# Solo_Board1.net
KiCad netlist of a schematic drawn in Altium Designer
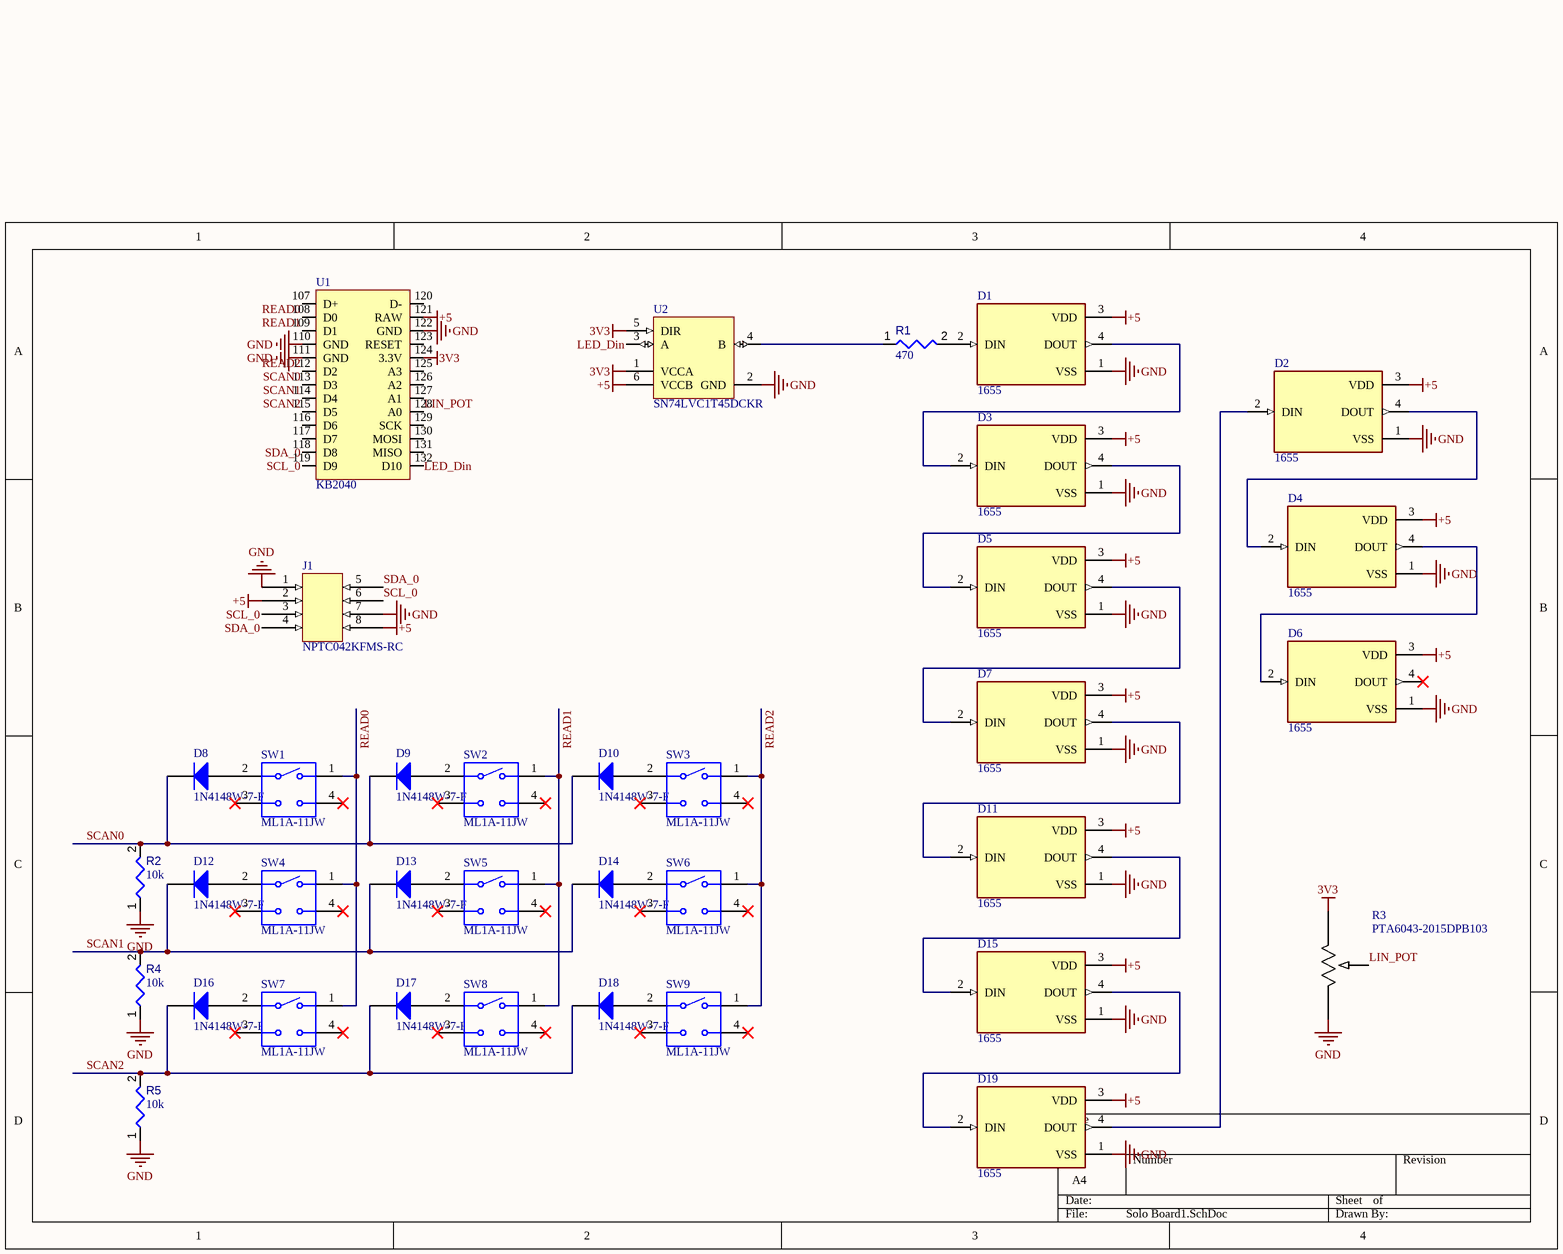
[diagram p0: Solo Board1.SchDoc]

(export (version "E")
  (design (tool "Eeschema 10.0.6"))
  (components
    (comp (ref "D1")
      (value "1655")
      (footprint "LED_1655")
      (description "Ws2812b 5050 Rgb Led With Integrated Driver Chip Pack Of 10")
      (libsource (lib "Joshua Lobe") (part "1655"))
    )
    (comp (ref "D2")
      (value "1655")
      (footprint "LED_1655")
      (description "Ws2812b 5050 Rgb Led With Integrated Driver Chip Pack Of 10")
      (libsource (lib "Joshua Lobe") (part "1655"))
    )
    (comp (ref "D3")
      (value "1655")
      (footprint "LED_1655")
      (description "Ws2812b 5050 Rgb Led With Integrated Driver Chip Pack Of 10")
      (libsource (lib "Joshua Lobe") (part "1655"))
    )
    (comp (ref "D4")
      (value "1655")
      (footprint "LED_1655")
      (description "Ws2812b 5050 Rgb Led With Integrated Driver Chip Pack Of 10")
      (libsource (lib "Joshua Lobe") (part "1655"))
    )
    (comp (ref "D5")
      (value "1655")
      (footprint "LED_1655")
      (description "Ws2812b 5050 Rgb Led With Integrated Driver Chip Pack Of 10")
      (libsource (lib "Joshua Lobe") (part "1655"))
    )
    (comp (ref "D6")
      (value "1655")
      (footprint "LED_1655")
      (description "Ws2812b 5050 Rgb Led With Integrated Driver Chip Pack Of 10")
      (libsource (lib "Joshua Lobe") (part "1655"))
    )
    (comp (ref "D7")
      (value "1655")
      (footprint "LED_1655")
      (description "Ws2812b 5050 Rgb Led With Integrated Driver Chip Pack Of 10")
      (libsource (lib "Joshua Lobe") (part "1655"))
    )
    (comp (ref "D8")
      (value "1N4148W-7-F")
      (footprint "DIOD-SOD123-2_V")
      (description "Fast Switching Diode, 100 V, 0.15 A, -65 to 150 degC, 2-Pin?SOD123, RoHS, Tape and Reel")
      (fields (field (name "MANUFACTURER") "DiodesIncorporated"))
      (libsource (lib "Altium Content Vault") (part "D-AK-2"))
    )
    (comp (ref "D9")
      (value "1N4148W-7-F")
      (footprint "DIOD-SOD123-2_V")
      (description "Fast Switching Diode, 100 V, 0.15 A, -65 to 150 degC, 2-Pin?SOD123, RoHS, Tape and Reel")
      (fields (field (name "MANUFACTURER") "DiodesIncorporated"))
      (libsource (lib "Altium Content Vault") (part "D-AK-2"))
    )
    (comp (ref "D10")
      (value "1N4148W-7-F")
      (footprint "DIOD-SOD123-2_V")
      (description "Fast Switching Diode, 100 V, 0.15 A, -65 to 150 degC, 2-Pin?SOD123, RoHS, Tape and Reel")
      (fields (field (name "MANUFACTURER") "DiodesIncorporated"))
      (libsource (lib "Altium Content Vault") (part "D-AK-2"))
    )
    (comp (ref "D11")
      (value "1655")
      (footprint "LED_1655")
      (description "Ws2812b 5050 Rgb Led With Integrated Driver Chip Pack Of 10")
      (libsource (lib "Joshua Lobe") (part "1655"))
    )
    (comp (ref "D12")
      (value "1N4148W-7-F")
      (footprint "DIOD-SOD123-2_V")
      (description "Fast Switching Diode, 100 V, 0.15 A, -65 to 150 degC, 2-Pin?SOD123, RoHS, Tape and Reel")
      (fields (field (name "MANUFACTURER") "DiodesIncorporated"))
      (libsource (lib "Altium Content Vault") (part "D-AK-2"))
    )
    (comp (ref "D13")
      (value "1N4148W-7-F")
      (footprint "DIOD-SOD123-2_V")
      (description "Fast Switching Diode, 100 V, 0.15 A, -65 to 150 degC, 2-Pin?SOD123, RoHS, Tape and Reel")
      (fields (field (name "MANUFACTURER") "DiodesIncorporated"))
      (libsource (lib "Altium Content Vault") (part "D-AK-2"))
    )
    (comp (ref "D14")
      (value "1N4148W-7-F")
      (footprint "DIOD-SOD123-2_V")
      (description "Fast Switching Diode, 100 V, 0.15 A, -65 to 150 degC, 2-Pin?SOD123, RoHS, Tape and Reel")
      (fields (field (name "MANUFACTURER") "DiodesIncorporated"))
      (libsource (lib "Altium Content Vault") (part "D-AK-2"))
    )
    (comp (ref "D15")
      (value "1655")
      (footprint "LED_1655")
      (description "Ws2812b 5050 Rgb Led With Integrated Driver Chip Pack Of 10")
      (libsource (lib "Joshua Lobe") (part "1655"))
    )
    (comp (ref "D16")
      (value "1N4148W-7-F")
      (footprint "DIOD-SOD123-2_V")
      (description "Fast Switching Diode, 100 V, 0.15 A, -65 to 150 degC, 2-Pin?SOD123, RoHS, Tape and Reel")
      (fields (field (name "MANUFACTURER") "DiodesIncorporated"))
      (libsource (lib "Altium Content Vault") (part "D-AK-2"))
    )
    (comp (ref "D17")
      (value "1N4148W-7-F")
      (footprint "DIOD-SOD123-2_V")
      (description "Fast Switching Diode, 100 V, 0.15 A, -65 to 150 degC, 2-Pin?SOD123, RoHS, Tape and Reel")
      (fields (field (name "MANUFACTURER") "DiodesIncorporated"))
      (libsource (lib "Altium Content Vault") (part "D-AK-2"))
    )
    (comp (ref "D18")
      (value "1N4148W-7-F")
      (footprint "DIOD-SOD123-2_V")
      (description "Fast Switching Diode, 100 V, 0.15 A, -65 to 150 degC, 2-Pin?SOD123, RoHS, Tape and Reel")
      (fields (field (name "MANUFACTURER") "DiodesIncorporated"))
      (libsource (lib "Altium Content Vault") (part "D-AK-2"))
    )
    (comp (ref "D19")
      (value "1655")
      (footprint "LED_1655")
      (description "Ws2812b 5050 Rgb Led With Integrated Driver Chip Pack Of 10")
      (libsource (lib "Joshua Lobe") (part "1655"))
    )
    (comp (ref "J1")
      (value "NPTC042KFMS-RC")
      (footprint "NPTC042KFMS-RC-Footprint-1")
      (libsource (lib "Joshua Lobe") (part "NPTC042KFMS-RC-Symbol-1"))
    )
    (comp (ref "R1")
      (value "470")
      (footprint "RESC0805(2012)_L")
      (description "Chip Resistor, 470 Ohms, +/-5%, 125 mW, -55 to 155 degC, 0805")
      (fields (field (name "TOLERANCE") "5%") (field (name "POWER") "125mW"))
      (libsource (lib "Joshua Lobe") (part "RES-2"))
    )
    (comp (ref "R2")
      (value "10k")
      (footprint "RESC2013X50X35ML15T15")
      (description "Chip Resistor, 10 KOhm, +/- 1%, 125 mW, -55 to 155 degC, 0805 (2012 Metric)")
      (fields (field (name "TOLERANCE") "1%") (field (name "POWER") "125mW"))
      (libsource (lib "Joshua Lobe") (part "RES-2"))
    )
    (comp (ref "R3")
      (value "PTA6043-2015DPB103")
      (footprint "POT_PTA6043")
      (description "No Description Available")
      (libsource (lib "Schlib1") (part "PTA6043-2015DPB103"))
    )
    (comp (ref "R4")
      (value "10k")
      (footprint "RESC2013X50X35ML15T15")
      (description "Chip Resistor, 10 KOhm, +/- 1%, 125 mW, -55 to 155 degC, 0805 (2012 Metric)")
      (fields (field (name "TOLERANCE") "1%") (field (name "POWER") "125mW"))
      (libsource (lib "Joshua Lobe") (part "RES-2"))
    )
    (comp (ref "R5")
      (value "10k")
      (footprint "RESC2013X50X35ML15T15")
      (description "Chip Resistor, 10 KOhm, +/- 1%, 125 mW, -55 to 155 degC, 0805 (2012 Metric)")
      (fields (field (name "TOLERANCE") "1%") (field (name "POWER") "125mW"))
      (libsource (lib "Joshua Lobe") (part "RES-2"))
    )
    (comp (ref "SW1")
      (value "ML1A-11JW")
      (footprint "CHRY-ML1A-11JW_V")
      (description "Keyboard Switch, SPST, IP40, 12 V Max, 10 mA Max, -40 to 70 degC, 4-Pin THD, RoHS, Bulk")
      (fields (field (name "MANUFACTURER") "Cherry") (field (name "PART NO") "ML1A11JW"))
      (libsource (lib "Altium Content Vault") (part "KEYSW-SPST-J-4"))
    )
    (comp (ref "SW2")
      (value "ML1A-11JW")
      (footprint "CHRY-ML1A-11JW_V")
      (description "Keyboard Switch, SPST, IP40, 12 V Max, 10 mA Max, -40 to 70 degC, 4-Pin THD, RoHS, Bulk")
      (fields (field (name "MANUFACTURER") "Cherry") (field (name "PART NO") "ML1A11JW"))
      (libsource (lib "Altium Content Vault") (part "KEYSW-SPST-J-4"))
    )
    (comp (ref "SW3")
      (value "ML1A-11JW")
      (footprint "CHRY-ML1A-11JW_V")
      (description "Keyboard Switch, SPST, IP40, 12 V Max, 10 mA Max, -40 to 70 degC, 4-Pin THD, RoHS, Bulk")
      (fields (field (name "MANUFACTURER") "Cherry") (field (name "PART NO") "ML1A11JW"))
      (libsource (lib "Altium Content Vault") (part "KEYSW-SPST-J-4"))
    )
    (comp (ref "SW4")
      (value "ML1A-11JW")
      (footprint "CHRY-ML1A-11JW_V")
      (description "Keyboard Switch, SPST, IP40, 12 V Max, 10 mA Max, -40 to 70 degC, 4-Pin THD, RoHS, Bulk")
      (fields (field (name "MANUFACTURER") "Cherry") (field (name "PART NO") "ML1A11JW"))
      (libsource (lib "Altium Content Vault") (part "KEYSW-SPST-J-4"))
    )
    (comp (ref "SW5")
      (value "ML1A-11JW")
      (footprint "CHRY-ML1A-11JW_V")
      (description "Keyboard Switch, SPST, IP40, 12 V Max, 10 mA Max, -40 to 70 degC, 4-Pin THD, RoHS, Bulk")
      (fields (field (name "MANUFACTURER") "Cherry") (field (name "PART NO") "ML1A11JW"))
      (libsource (lib "Altium Content Vault") (part "KEYSW-SPST-J-4"))
    )
    (comp (ref "SW6")
      (value "ML1A-11JW")
      (footprint "CHRY-ML1A-11JW_V")
      (description "Keyboard Switch, SPST, IP40, 12 V Max, 10 mA Max, -40 to 70 degC, 4-Pin THD, RoHS, Bulk")
      (fields (field (name "MANUFACTURER") "Cherry") (field (name "PART NO") "ML1A11JW"))
      (libsource (lib "Altium Content Vault") (part "KEYSW-SPST-J-4"))
    )
    (comp (ref "SW7")
      (value "ML1A-11JW")
      (footprint "CHRY-ML1A-11JW_V")
      (description "Keyboard Switch, SPST, IP40, 12 V Max, 10 mA Max, -40 to 70 degC, 4-Pin THD, RoHS, Bulk")
      (fields (field (name "MANUFACTURER") "Cherry") (field (name "PART NO") "ML1A11JW"))
      (libsource (lib "Altium Content Vault") (part "KEYSW-SPST-J-4"))
    )
    (comp (ref "SW8")
      (value "ML1A-11JW")
      (footprint "CHRY-ML1A-11JW_V")
      (description "Keyboard Switch, SPST, IP40, 12 V Max, 10 mA Max, -40 to 70 degC, 4-Pin THD, RoHS, Bulk")
      (fields (field (name "MANUFACTURER") "Cherry") (field (name "PART NO") "ML1A11JW"))
      (libsource (lib "Altium Content Vault") (part "KEYSW-SPST-J-4"))
    )
    (comp (ref "SW9")
      (value "ML1A-11JW")
      (footprint "CHRY-ML1A-11JW_V")
      (description "Keyboard Switch, SPST, IP40, 12 V Max, 10 mA Max, -40 to 70 degC, 4-Pin THD, RoHS, Bulk")
      (fields (field (name "MANUFACTURER") "Cherry") (field (name "PART NO") "ML1A11JW"))
      (libsource (lib "Altium Content Vault") (part "KEYSW-SPST-J-4"))
    )
    (comp (ref "U1")
      (value "KB2040")
      (footprint "KB2040")
      (description "Keyboard IC breakour board")
      (libsource (lib "Schlib1") (part "KB2040"))
    )
    (comp (ref "U2")
      (value "SN74LVC1T45DCKR")
      (footprint "DCK0006A_M")
      (fields
        (field (name "MANUFACTURER") "Texas Instruments")
        (field (name "GENERIC PART NUMBER") "SN74LVC1T45")
      )
      (libsource (lib "Altium Content Vault") (part "TI-SN74XVC1T45-6"))
    )
  )
  (nets
    (net (code "1") (name "+5") (class "Default")
      (node (ref "D1") (pin "3") (pinfunction "VDD_3") (pintype "power_in"))
      (node (ref "D11") (pin "3") (pinfunction "VDD_3") (pintype "power_in"))
      (node (ref "D15") (pin "3") (pinfunction "VDD_3") (pintype "power_in"))
      (node (ref "D19") (pin "3") (pinfunction "VDD_3") (pintype "power_in"))
      (node (ref "D2") (pin "3") (pinfunction "VDD_3") (pintype "power_in"))
      (node (ref "D3") (pin "3") (pinfunction "VDD_3") (pintype "power_in"))
      (node (ref "D4") (pin "3") (pinfunction "VDD_3") (pintype "power_in"))
      (node (ref "D5") (pin "3") (pinfunction "VDD_3") (pintype "power_in"))
      (node (ref "D6") (pin "3") (pinfunction "VDD_3") (pintype "power_in"))
      (node (ref "D7") (pin "3") (pinfunction "VDD_3") (pintype "power_in"))
      (node (ref "J1") (pin "2") (pinfunction "2_2") (pintype "input"))
      (node (ref "J1") (pin "8") (pinfunction "8_8") (pintype "input"))
      (node (ref "U1") (pin "121") (pinfunction "RAW_121") (pintype "passive"))
      (node (ref "U2") (pin "6") (pinfunction "VCCB_6") (pintype "power_in"))
    )
    (net (code "3") (name "/LED_Din") (class "Default")
      (node (ref "U1") (pin "132") (pinfunction "D10_132") (pintype "passive"))
      (node (ref "U2") (pin "3") (pinfunction "A_3") (pintype "bidirectional"))
    )
    (net (code "4") (name "/LIN_POT") (class "Default")
      (node (ref "R3") (pin "2") (pinfunction "2_2") (pintype "passive"))
      (node (ref "U1") (pin "128") (pinfunction "A0_128") (pintype "passive"))
    )
    (net (code "5") (name "/READ0") (class "Default")
      (node (ref "SW1") (pin "1") (pinfunction "1_1") (pintype "passive"))
      (node (ref "SW4") (pin "1") (pinfunction "1_1") (pintype "passive"))
      (node (ref "SW7") (pin "1") (pinfunction "1_1") (pintype "passive"))
      (node (ref "U1") (pin "108") (pinfunction "D0_108") (pintype "passive"))
    )
    (net (code "6") (name "/READ1") (class "Default")
      (node (ref "SW2") (pin "1") (pinfunction "1_1") (pintype "passive"))
      (node (ref "SW5") (pin "1") (pinfunction "1_1") (pintype "passive"))
      (node (ref "SW8") (pin "1") (pinfunction "1_1") (pintype "passive"))
      (node (ref "U1") (pin "109") (pinfunction "D1_109") (pintype "passive"))
    )
    (net (code "7") (name "/READ2") (class "Default")
      (node (ref "SW3") (pin "1") (pinfunction "1_1") (pintype "passive"))
      (node (ref "SW6") (pin "1") (pinfunction "1_1") (pintype "passive"))
      (node (ref "SW9") (pin "1") (pinfunction "1_1") (pintype "passive"))
      (node (ref "U1") (pin "112") (pinfunction "D2_112") (pintype "passive"))
    )
    (net (code "8") (name "/SCAN0") (class "Default")
      (node (ref "D10") (pin "2") (pinfunction "K_2") (pintype "passive"))
      (node (ref "D8") (pin "2") (pinfunction "K_2") (pintype "passive"))
      (node (ref "D9") (pin "2") (pinfunction "K_2") (pintype "passive"))
      (node (ref "R2") (pin "2") (pinfunction "2_2") (pintype "passive"))
      (node (ref "U1") (pin "113") (pinfunction "D3_113") (pintype "passive"))
    )
    (net (code "9") (name "/SCAN1") (class "Default")
      (node (ref "D12") (pin "2") (pinfunction "K_2") (pintype "passive"))
      (node (ref "D13") (pin "2") (pinfunction "K_2") (pintype "passive"))
      (node (ref "D14") (pin "2") (pinfunction "K_2") (pintype "passive"))
      (node (ref "R4") (pin "2") (pinfunction "2_2") (pintype "passive"))
      (node (ref "U1") (pin "114") (pinfunction "D4_114") (pintype "passive"))
    )
    (net (code "10") (name "/SCAN2") (class "Default")
      (node (ref "D16") (pin "2") (pinfunction "K_2") (pintype "passive"))
      (node (ref "D17") (pin "2") (pinfunction "K_2") (pintype "passive"))
      (node (ref "D18") (pin "2") (pinfunction "K_2") (pintype "passive"))
      (node (ref "R5") (pin "2") (pinfunction "2_2") (pintype "passive"))
      (node (ref "U1") (pin "115") (pinfunction "D5_115") (pintype "passive"))
    )
    (net (code "11") (name "/SCL_0") (class "Default")
      (node (ref "J1") (pin "3") (pinfunction "3_3") (pintype "input"))
      (node (ref "J1") (pin "6") (pinfunction "6_6") (pintype "input"))
      (node (ref "U1") (pin "119") (pinfunction "D9_119") (pintype "passive"))
    )
    (net (code "12") (name "/SDA_0") (class "Default")
      (node (ref "J1") (pin "4") (pinfunction "4_4") (pintype "input"))
      (node (ref "J1") (pin "5") (pinfunction "5_5") (pintype "input"))
      (node (ref "U1") (pin "118") (pinfunction "D8_118") (pintype "passive"))
    )
    (net (code "13") (name "3V3") (class "Default")
      (node (ref "R3") (pin "3") (pinfunction "3_3") (pintype "passive"))
      (node (ref "U1") (pin "124") (pinfunction "3.3V_124") (pintype "passive"))
      (node (ref "U2") (pin "1") (pinfunction "VCCA_1") (pintype "power_in"))
      (node (ref "U2") (pin "5") (pinfunction "DIR_5") (pintype "input"))
    )
    (net (code "14") (name "GND") (class "Default")
      (node (ref "D1") (pin "1") (pinfunction "VSS_1") (pintype "power_in"))
      (node (ref "D11") (pin "1") (pinfunction "VSS_1") (pintype "power_in"))
      (node (ref "D15") (pin "1") (pinfunction "VSS_1") (pintype "power_in"))
      (node (ref "D19") (pin "1") (pinfunction "VSS_1") (pintype "power_in"))
      (node (ref "D2") (pin "1") (pinfunction "VSS_1") (pintype "power_in"))
      (node (ref "D3") (pin "1") (pinfunction "VSS_1") (pintype "power_in"))
      (node (ref "D4") (pin "1") (pinfunction "VSS_1") (pintype "power_in"))
      (node (ref "D5") (pin "1") (pinfunction "VSS_1") (pintype "power_in"))
      (node (ref "D6") (pin "1") (pinfunction "VSS_1") (pintype "power_in"))
      (node (ref "D7") (pin "1") (pinfunction "VSS_1") (pintype "power_in"))
      (node (ref "J1") (pin "1") (pinfunction "1_1") (pintype "input"))
      (node (ref "J1") (pin "7") (pinfunction "7_7") (pintype "input"))
      (node (ref "R2") (pin "1") (pinfunction "1_1") (pintype "passive"))
      (node (ref "R3") (pin "1") (pinfunction "1_1") (pintype "passive"))
      (node (ref "R4") (pin "1") (pinfunction "1_1") (pintype "passive"))
      (node (ref "R5") (pin "1") (pinfunction "1_1") (pintype "passive"))
      (node (ref "U1") (pin "110") (pinfunction "GND_110") (pintype "passive"))
      (node (ref "U1") (pin "111") (pinfunction "GND_111") (pintype "passive"))
      (node (ref "U1") (pin "122") (pinfunction "GND_122") (pintype "passive"))
      (node (ref "U2") (pin "2") (pinfunction "GND_2") (pintype "power_in"))
    )
    (net (code "15") (name "Net-(D1-DIN)") (class "Default")
      (node (ref "D1") (pin "2") (pinfunction "DIN_2") (pintype "input"))
      (node (ref "R1") (pin "2") (pinfunction "2_2") (pintype "passive"))
    )
    (net (code "16") (name "Net-(D1-DOUT)") (class "Default")
      (node (ref "D1") (pin "4") (pinfunction "DOUT_4") (pintype "output"))
      (node (ref "D3") (pin "2") (pinfunction "DIN_2") (pintype "input"))
    )
    (net (code "17") (name "Net-(D2-DOUT)") (class "Default")
      (node (ref "D2") (pin "4") (pinfunction "DOUT_4") (pintype "output"))
      (node (ref "D4") (pin "2") (pinfunction "DIN_2") (pintype "input"))
    )
    (net (code "18") (name "Net-(D3-DOUT)") (class "Default")
      (node (ref "D3") (pin "4") (pinfunction "DOUT_4") (pintype "output"))
      (node (ref "D5") (pin "2") (pinfunction "DIN_2") (pintype "input"))
    )
    (net (code "19") (name "Net-(D4-DOUT)") (class "Default")
      (node (ref "D4") (pin "4") (pinfunction "DOUT_4") (pintype "output"))
      (node (ref "D6") (pin "2") (pinfunction "DIN_2") (pintype "input"))
    )
    (net (code "20") (name "Net-(D5-DOUT)") (class "Default")
      (node (ref "D5") (pin "4") (pinfunction "DOUT_4") (pintype "output"))
      (node (ref "D7") (pin "2") (pinfunction "DIN_2") (pintype "input"))
    )
    (net (code "21") (name "Net-(D8-A)") (class "Default")
      (node (ref "D8") (pin "1") (pinfunction "A_1") (pintype "passive"))
      (node (ref "SW1") (pin "2") (pinfunction "2_2") (pintype "passive"))
    )
    (net (code "22") (name "Net-(D9-A)") (class "Default")
      (node (ref "D9") (pin "1") (pinfunction "A_1") (pintype "passive"))
      (node (ref "SW2") (pin "2") (pinfunction "2_2") (pintype "passive"))
    )
    (net (code "23") (name "Net-(D10-A)") (class "Default")
      (node (ref "D10") (pin "1") (pinfunction "A_1") (pintype "passive"))
      (node (ref "SW3") (pin "2") (pinfunction "2_2") (pintype "passive"))
    )
    (net (code "24") (name "Net-(D11-DIN)") (class "Default")
      (node (ref "D11") (pin "2") (pinfunction "DIN_2") (pintype "input"))
      (node (ref "D7") (pin "4") (pinfunction "DOUT_4") (pintype "output"))
    )
    (net (code "25") (name "Net-(D11-DOUT)") (class "Default")
      (node (ref "D11") (pin "4") (pinfunction "DOUT_4") (pintype "output"))
      (node (ref "D15") (pin "2") (pinfunction "DIN_2") (pintype "input"))
    )
    (net (code "26") (name "Net-(D12-A)") (class "Default")
      (node (ref "D12") (pin "1") (pinfunction "A_1") (pintype "passive"))
      (node (ref "SW4") (pin "2") (pinfunction "2_2") (pintype "passive"))
    )
    (net (code "27") (name "Net-(D13-A)") (class "Default")
      (node (ref "D13") (pin "1") (pinfunction "A_1") (pintype "passive"))
      (node (ref "SW5") (pin "2") (pinfunction "2_2") (pintype "passive"))
    )
    (net (code "28") (name "Net-(D14-A)") (class "Default")
      (node (ref "D14") (pin "1") (pinfunction "A_1") (pintype "passive"))
      (node (ref "SW6") (pin "2") (pinfunction "2_2") (pintype "passive"))
    )
    (net (code "29") (name "Net-(D15-DOUT)") (class "Default")
      (node (ref "D15") (pin "4") (pinfunction "DOUT_4") (pintype "output"))
      (node (ref "D19") (pin "2") (pinfunction "DIN_2") (pintype "input"))
    )
    (net (code "30") (name "Net-(D16-A)") (class "Default")
      (node (ref "D16") (pin "1") (pinfunction "A_1") (pintype "passive"))
      (node (ref "SW7") (pin "2") (pinfunction "2_2") (pintype "passive"))
    )
    (net (code "31") (name "Net-(D17-A)") (class "Default")
      (node (ref "D17") (pin "1") (pinfunction "A_1") (pintype "passive"))
      (node (ref "SW8") (pin "2") (pinfunction "2_2") (pintype "passive"))
    )
    (net (code "32") (name "Net-(D18-A)") (class "Default")
      (node (ref "D18") (pin "1") (pinfunction "A_1") (pintype "passive"))
      (node (ref "SW9") (pin "2") (pinfunction "2_2") (pintype "passive"))
    )
    (net (code "33") (name "Net-(D19-DOUT)") (class "Default")
      (node (ref "D19") (pin "4") (pinfunction "DOUT_4") (pintype "output"))
      (node (ref "D2") (pin "2") (pinfunction "DIN_2") (pintype "input"))
    )
    (net (code "34") (name "Net-(U2-B)") (class "Default")
      (node (ref "R1") (pin "1") (pinfunction "1_1") (pintype "passive"))
      (node (ref "U2") (pin "4") (pinfunction "B_4") (pintype "bidirectional"))
    )
    (net (code "35") (name "unconnected-(D6-DOUT-Pad4)") (class "Default")
      (node (ref "D6") (pin "4") (pinfunction "DOUT_4") (pintype "output+no_connect"))
    )
    (net (code "36") (name "unconnected-(SW1-Pad3)") (class "Default")
      (node (ref "SW1") (pin "3") (pinfunction "3_3") (pintype "passive+no_connect"))
    )
    (net (code "37") (name "unconnected-(SW1-Pad4)") (class "Default")
      (node (ref "SW1") (pin "4") (pinfunction "4_4") (pintype "passive+no_connect"))
    )
    (net (code "38") (name "unconnected-(SW2-Pad3)") (class "Default")
      (node (ref "SW2") (pin "3") (pinfunction "3_3") (pintype "passive+no_connect"))
    )
    (net (code "39") (name "unconnected-(SW2-Pad4)") (class "Default")
      (node (ref "SW2") (pin "4") (pinfunction "4_4") (pintype "passive+no_connect"))
    )
    (net (code "40") (name "unconnected-(SW3-Pad3)") (class "Default")
      (node (ref "SW3") (pin "3") (pinfunction "3_3") (pintype "passive+no_connect"))
    )
    (net (code "41") (name "unconnected-(SW3-Pad4)") (class "Default")
      (node (ref "SW3") (pin "4") (pinfunction "4_4") (pintype "passive+no_connect"))
    )
    (net (code "42") (name "unconnected-(SW4-Pad3)") (class "Default")
      (node (ref "SW4") (pin "3") (pinfunction "3_3") (pintype "passive+no_connect"))
    )
    (net (code "43") (name "unconnected-(SW4-Pad4)") (class "Default")
      (node (ref "SW4") (pin "4") (pinfunction "4_4") (pintype "passive+no_connect"))
    )
    (net (code "44") (name "unconnected-(SW5-Pad3)") (class "Default")
      (node (ref "SW5") (pin "3") (pinfunction "3_3") (pintype "passive+no_connect"))
    )
    (net (code "45") (name "unconnected-(SW5-Pad4)") (class "Default")
      (node (ref "SW5") (pin "4") (pinfunction "4_4") (pintype "passive+no_connect"))
    )
    (net (code "46") (name "unconnected-(SW6-Pad3)") (class "Default")
      (node (ref "SW6") (pin "3") (pinfunction "3_3") (pintype "passive+no_connect"))
    )
    (net (code "47") (name "unconnected-(SW6-Pad4)") (class "Default")
      (node (ref "SW6") (pin "4") (pinfunction "4_4") (pintype "passive+no_connect"))
    )
    (net (code "48") (name "unconnected-(SW7-Pad3)") (class "Default")
      (node (ref "SW7") (pin "3") (pinfunction "3_3") (pintype "passive+no_connect"))
    )
    (net (code "49") (name "unconnected-(SW7-Pad4)") (class "Default")
      (node (ref "SW7") (pin "4") (pinfunction "4_4") (pintype "passive+no_connect"))
    )
    (net (code "50") (name "unconnected-(SW8-Pad3)") (class "Default")
      (node (ref "SW8") (pin "3") (pinfunction "3_3") (pintype "passive+no_connect"))
    )
    (net (code "51") (name "unconnected-(SW8-Pad4)") (class "Default")
      (node (ref "SW8") (pin "4") (pinfunction "4_4") (pintype "passive+no_connect"))
    )
    (net (code "52") (name "unconnected-(SW9-Pad3)") (class "Default")
      (node (ref "SW9") (pin "3") (pinfunction "3_3") (pintype "passive+no_connect"))
    )
    (net (code "53") (name "unconnected-(SW9-Pad4)") (class "Default")
      (node (ref "SW9") (pin "4") (pinfunction "4_4") (pintype "passive+no_connect"))
    )
    (net (code "54") (name "unconnected-(U1-A1-Pad127)") (class "Default")
      (node (ref "U1") (pin "127") (pinfunction "A1_127") (pintype "passive"))
    )
    (net (code "55") (name "unconnected-(U1-A2-Pad126)") (class "Default")
      (node (ref "U1") (pin "126") (pinfunction "A2_126") (pintype "passive"))
    )
    (net (code "56") (name "unconnected-(U1-A3-Pad125)") (class "Default")
      (node (ref "U1") (pin "125") (pinfunction "A3_125") (pintype "passive"))
    )
    (net (code "57") (name "unconnected-(U1-D+-Pad107)") (class "Default")
      (node (ref "U1") (pin "107") (pinfunction "D+_107") (pintype "passive"))
    )
    (net (code "58") (name "unconnected-(U1-D--Pad120)") (class "Default")
      (node (ref "U1") (pin "120") (pinfunction "D-_120") (pintype "passive"))
    )
    (net (code "59") (name "unconnected-(U1-D6-Pad116)") (class "Default")
      (node (ref "U1") (pin "116") (pinfunction "D6_116") (pintype "passive"))
    )
    (net (code "60") (name "unconnected-(U1-D7-Pad117)") (class "Default")
      (node (ref "U1") (pin "117") (pinfunction "D7_117") (pintype "passive"))
    )
    (net (code "61") (name "unconnected-(U1-MISO-Pad131)") (class "Default")
      (node (ref "U1") (pin "131") (pinfunction "MISO_131") (pintype "passive"))
    )
    (net (code "62") (name "unconnected-(U1-MOSI-Pad130)") (class "Default")
      (node (ref "U1") (pin "130") (pinfunction "MOSI_130") (pintype "passive"))
    )
    (net (code "63") (name "unconnected-(U1-RESET-Pad123)") (class "Default")
      (node (ref "U1") (pin "123") (pinfunction "RESET_123") (pintype "passive"))
    )
    (net (code "64") (name "unconnected-(U1-SCK-Pad129)") (class "Default")
      (node (ref "U1") (pin "129") (pinfunction "SCK_129") (pintype "passive"))
    )
  )
)
